# ADC_Level.net
KiCad netlist of a schematic drawn in Altium Designer
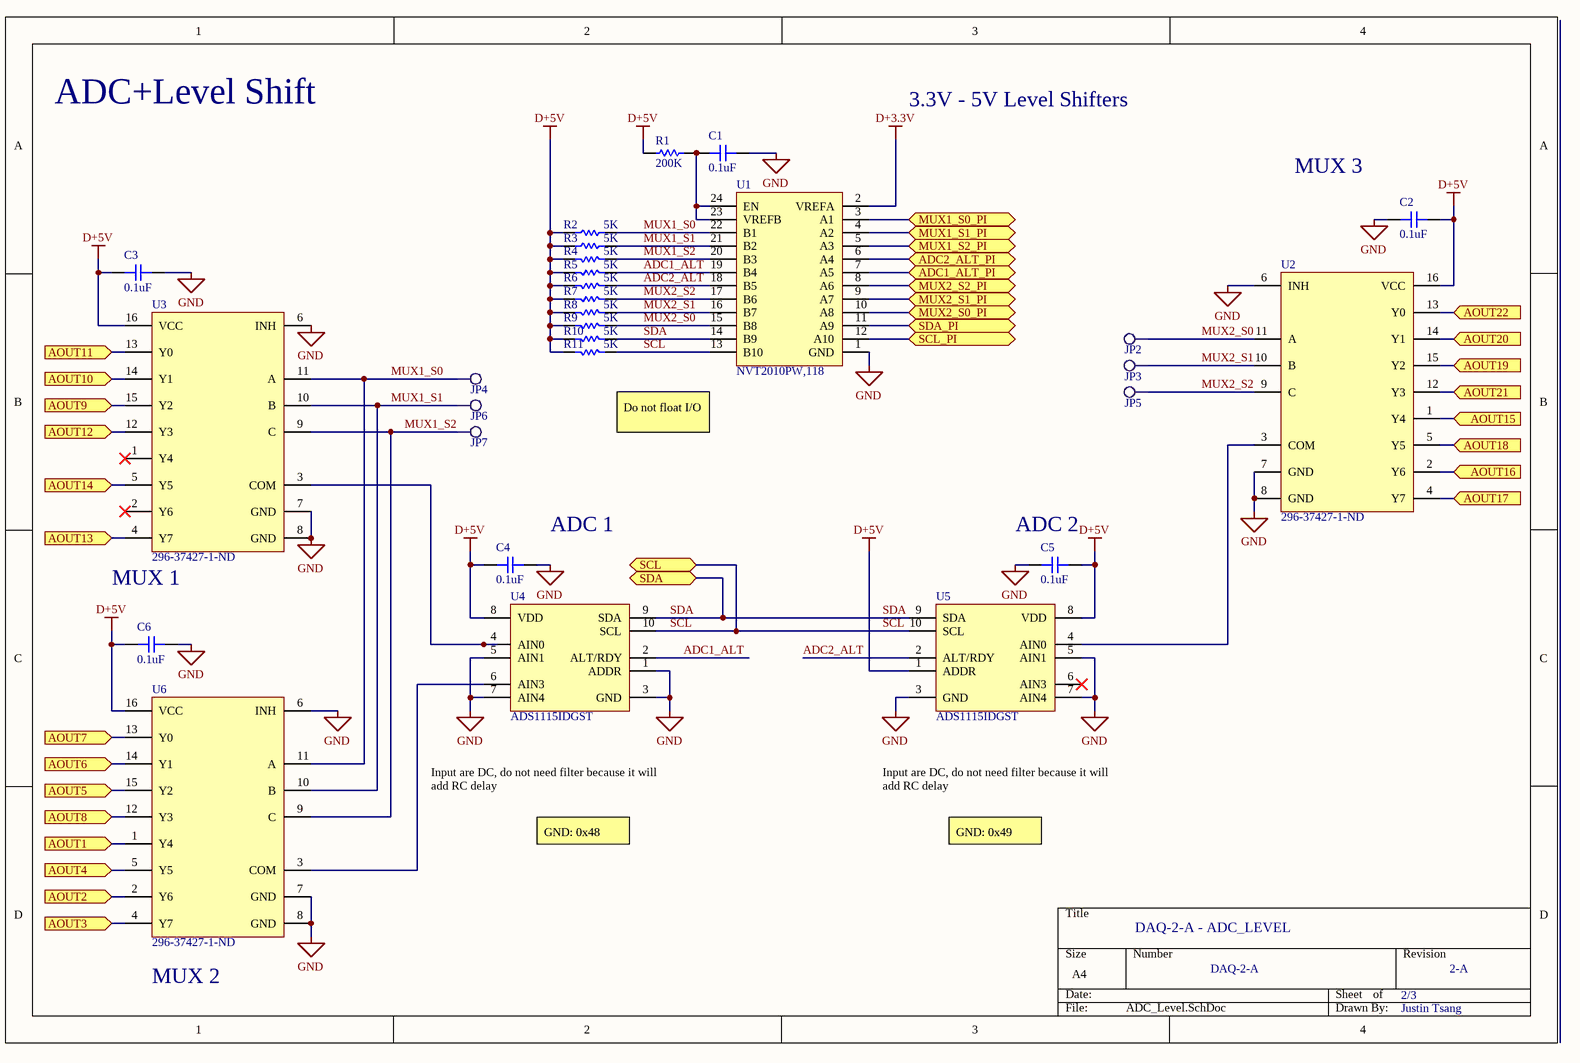
[diagram p0: ADC_Level.SchDoc]

(export (version "E")
  (design (tool "Eeschema 10.0.6"))
  (components
    (comp (ref "C1")
      (value "0.1uF")
      (footprint "CAP-0603")
      (description "CAP CER 0.1UF 16V X7R 0603")
      (fields
        (field (name "MANUFACTURER") "KEMET")
        (field (name "MANUFACTURER PART NUMBER") "C0603C104M4RACTU")
      )
      (libsource (lib "Capacitors") (part "0603-0.1uF-16V"))
    )
    (comp (ref "C2")
      (value "0.1uF")
      (footprint "CAP-0603")
      (description "CAP CER 0.1UF 16V X7R 0603")
      (fields
        (field (name "MANUFACTURER") "KEMET")
        (field (name "MANUFACTURER PART NUMBER") "C0603C104M4RACTU")
      )
      (libsource (lib "Capacitors") (part "0603-0.1uF-16V"))
    )
    (comp (ref "C3")
      (value "0.1uF")
      (footprint "CAP-0603")
      (description "CAP CER 0.1UF 16V X7R 0603")
      (fields
        (field (name "MANUFACTURER") "KEMET")
        (field (name "MANUFACTURER PART NUMBER") "C0603C104M4RACTU")
      )
      (libsource (lib "Capacitors") (part "0603-0.1uF-16V"))
    )
    (comp (ref "C4")
      (value "0.1uF")
      (footprint "CAP-0603")
      (description "CAP CER 0.1UF 16V X7R 0603")
      (fields
        (field (name "MANUFACTURER") "KEMET")
        (field (name "MANUFACTURER PART NUMBER") "C0603C104M4RACTU")
      )
      (libsource (lib "Capacitors") (part "0603-0.1uF-16V"))
    )
    (comp (ref "C5")
      (value "0.1uF")
      (footprint "CAP-0603")
      (description "CAP CER 0.1UF 16V X7R 0603")
      (fields
        (field (name "MANUFACTURER") "KEMET")
        (field (name "MANUFACTURER PART NUMBER") "C0603C104M4RACTU")
      )
      (libsource (lib "Capacitors") (part "0603-0.1uF-16V"))
    )
    (comp (ref "C6")
      (value "0.1uF")
      (footprint "CAP-0603")
      (description "CAP CER 0.1UF 16V X7R 0603")
      (fields
        (field (name "MANUFACTURER") "KEMET")
        (field (name "MANUFACTURER PART NUMBER") "C0603C104M4RACTU")
      )
      (libsource (lib "Capacitors") (part "0603-0.1uF-16V"))
    )
    (comp (ref "JP2")
      (value "Testpoint2")
      (footprint "TP2")
      (description "Single layer pad TP")
      (libsource (lib "Misc") (part "Testpoint2"))
    )
    (comp (ref "JP3")
      (value "Testpoint2")
      (footprint "TP2")
      (description "Single layer pad TP")
      (libsource (lib "Misc") (part "Testpoint2"))
    )
    (comp (ref "JP4")
      (value "Testpoint2")
      (footprint "TP2")
      (description "Single layer pad TP")
      (libsource (lib "Misc") (part "Testpoint2"))
    )
    (comp (ref "JP5")
      (value "Testpoint2")
      (footprint "TP2")
      (description "Single layer pad TP")
      (libsource (lib "Misc") (part "Testpoint2"))
    )
    (comp (ref "JP6")
      (value "Testpoint2")
      (footprint "TP2")
      (description "Single layer pad TP")
      (libsource (lib "Misc") (part "Testpoint2"))
    )
    (comp (ref "JP7")
      (value "Testpoint2")
      (footprint "TP2")
      (description "Single layer pad TP")
      (libsource (lib "Misc") (part "Testpoint2"))
    )
    (comp (ref "R1")
      (value "200K")
      (footprint "RES-0603")
      (description "RES SMD 200K OHM 1% 1/10W 0603")
      (libsource (lib "New_Parts") (part "0603-200KR"))
    )
    (comp (ref "R2")
      (value "5K")
      (footprint "RES-0603")
      (description "RES SMD 4.99K OHM 1% 1/10W 0603")
      (fields
        (field (name "MANUFACTURER") "Bourns")
        (field (name "MANUFACTURER PART NUMBER") "CR0603-FX-4991ELF")
      )
      (libsource (lib "Resistors") (part "0603-5KR"))
    )
    (comp (ref "R3")
      (value "5K")
      (footprint "RES-0603")
      (description "RES SMD 4.99K OHM 1% 1/10W 0603")
      (fields
        (field (name "MANUFACTURER") "Bourns")
        (field (name "MANUFACTURER PART NUMBER") "CR0603-FX-4991ELF")
      )
      (libsource (lib "Resistors") (part "0603-5KR"))
    )
    (comp (ref "R4")
      (value "5K")
      (footprint "RES-0603")
      (description "RES SMD 4.99K OHM 1% 1/10W 0603")
      (fields
        (field (name "MANUFACTURER") "Bourns")
        (field (name "MANUFACTURER PART NUMBER") "CR0603-FX-4991ELF")
      )
      (libsource (lib "Resistors") (part "0603-5KR"))
    )
    (comp (ref "R5")
      (value "5K")
      (footprint "RES-0603")
      (description "RES SMD 4.99K OHM 1% 1/10W 0603")
      (fields
        (field (name "MANUFACTURER") "Bourns")
        (field (name "MANUFACTURER PART NUMBER") "CR0603-FX-4991ELF")
      )
      (libsource (lib "Resistors") (part "0603-5KR"))
    )
    (comp (ref "R6")
      (value "5K")
      (footprint "RES-0603")
      (description "RES SMD 4.99K OHM 1% 1/10W 0603")
      (fields
        (field (name "MANUFACTURER") "Bourns")
        (field (name "MANUFACTURER PART NUMBER") "CR0603-FX-4991ELF")
      )
      (libsource (lib "Resistors") (part "0603-5KR"))
    )
    (comp (ref "R7")
      (value "5K")
      (footprint "RES-0603")
      (description "RES SMD 4.99K OHM 1% 1/10W 0603")
      (fields
        (field (name "MANUFACTURER") "Bourns")
        (field (name "MANUFACTURER PART NUMBER") "CR0603-FX-4991ELF")
      )
      (libsource (lib "Resistors") (part "0603-5KR"))
    )
    (comp (ref "R8")
      (value "5K")
      (footprint "RES-0603")
      (description "RES SMD 4.99K OHM 1% 1/10W 0603")
      (fields
        (field (name "MANUFACTURER") "Bourns")
        (field (name "MANUFACTURER PART NUMBER") "CR0603-FX-4991ELF")
      )
      (libsource (lib "Resistors") (part "0603-5KR"))
    )
    (comp (ref "R9")
      (value "5K")
      (footprint "RES-0603")
      (description "RES SMD 4.99K OHM 1% 1/10W 0603")
      (fields
        (field (name "MANUFACTURER") "Bourns")
        (field (name "MANUFACTURER PART NUMBER") "CR0603-FX-4991ELF")
      )
      (libsource (lib "Resistors") (part "0603-5KR"))
    )
    (comp (ref "R10")
      (value "5K")
      (footprint "RES-0603")
      (description "RES SMD 4.99K OHM 1% 1/10W 0603")
      (fields
        (field (name "MANUFACTURER") "Bourns")
        (field (name "MANUFACTURER PART NUMBER") "CR0603-FX-4991ELF")
      )
      (libsource (lib "Resistors") (part "0603-5KR"))
    )
    (comp (ref "R11")
      (value "5K")
      (footprint "RES-0603")
      (description "RES SMD 4.99K OHM 1% 1/10W 0603")
      (fields
        (field (name "MANUFACTURER") "Bourns")
        (field (name "MANUFACTURER PART NUMBER") "CR0603-FX-4991ELF")
      )
      (libsource (lib "Resistors") (part "0603-5KR"))
    )
    (comp (ref "U1")
      (value "NVT2010PW,118")
      (footprint "TSSOP65P660X110-24")
      (description "NVT2010PW/TSSOP24/REEL13//")
      (fields (field (name "MANUFACTURER") "NXP Semiconductors"))
      (libsource (lib "New_Parts") (part "IC_NVT2010PW"))
    )
    (comp (ref "U2")
      (value "296-37427-1-ND")
      (footprint "16-SOIC")
      (description "IC MUX/DEMUX 8X1 16SOIC")
      (fields
        (field (name "MANUFACTURER") "Texas Instruments")
        (field (name "MANUFACTURER PART NUMBER") "SN74LV4051ATDWRQ1")
      )
      (libsource (lib "") (part "MUX-SN74LV4051ATDWRQ1_1"))
    )
    (comp (ref "U3")
      (value "296-37427-1-ND")
      (footprint "16-SOIC")
      (description "IC MUX/DEMUX 8X1 16SOIC")
      (fields
        (field (name "MANUFACTURER") "Texas Instruments")
        (field (name "MANUFACTURER PART NUMBER") "SN74LV4051ATDWRQ1")
      )
      (libsource (lib "ICs") (part "MUX-SN74LV4051ATDWRQ1"))
    )
    (comp (ref "U4")
      (value "ADS1115IDGST")
      (footprint "VSSOP50P310X310-10P")
      (fields (field (name "MANUFACTURER") "Texas Instruments"))
      (libsource (lib "New_Parts") (part "IC_ADS1115"))
    )
    (comp (ref "U5")
      (value "ADS1115IDGST")
      (footprint "VSSOP50P310X310-10P")
      (fields (field (name "MANUFACTURER") "Texas Instruments"))
      (libsource (lib "") (part "IC_ADS1115_1"))
    )
    (comp (ref "U6")
      (value "296-37427-1-ND")
      (footprint "16-SOIC")
      (description "IC MUX/DEMUX 8X1 16SOIC")
      (fields
        (field (name "MANUFACTURER") "Texas Instruments")
        (field (name "MANUFACTURER PART NUMBER") "SN74LV4051ATDWRQ1")
      )
      (libsource (lib "ICs") (part "MUX-SN74LV4051ATDWRQ1"))
    )
  )
  (nets
    (net (code "1") (name "/ADC1_ALT") (class "Default")
      (node (ref "R5") (pin "2") (pinfunction "2_2") (pintype "passive"))
      (node (ref "U1") (pin "19") (pinfunction "B4_19") (pintype "passive"))
      (node (ref "U4") (pin "2") (pinfunction "ALT/RDY_2") (pintype "passive"))
    )
    (net (code "2") (name "/ADC1_ALT_PI") (class "Default")
      (node (ref "U1") (pin "7") (pinfunction "A5_7") (pintype "passive"))
    )
    (net (code "3") (name "/ADC2_ALT") (class "Default")
      (node (ref "R6") (pin "2") (pinfunction "2_2") (pintype "passive"))
      (node (ref "U1") (pin "18") (pinfunction "B5_18") (pintype "passive"))
      (node (ref "U5") (pin "2") (pinfunction "ALT/RDY_2") (pintype "passive"))
    )
    (net (code "4") (name "/ADC2_ALT_PI") (class "Default")
      (node (ref "U1") (pin "6") (pinfunction "A4_6") (pintype "passive"))
    )
    (net (code "5") (name "/AOUT1") (class "Default")
      (node (ref "U6") (pin "1") (pinfunction "Y4_1") (pintype "passive"))
    )
    (net (code "6") (name "/AOUT2") (class "Default")
      (node (ref "U6") (pin "2") (pinfunction "Y6_2") (pintype "passive"))
    )
    (net (code "7") (name "/AOUT3") (class "Default")
      (node (ref "U6") (pin "4") (pinfunction "Y7_4") (pintype "passive"))
    )
    (net (code "8") (name "/AOUT4") (class "Default")
      (node (ref "U6") (pin "5") (pinfunction "Y5_5") (pintype "passive"))
    )
    (net (code "9") (name "/AOUT5") (class "Default")
      (node (ref "U6") (pin "15") (pinfunction "Y2_15") (pintype "passive"))
    )
    (net (code "10") (name "/AOUT6") (class "Default")
      (node (ref "U6") (pin "14") (pinfunction "Y1_14") (pintype "passive"))
    )
    (net (code "11") (name "/AOUT7") (class "Default")
      (node (ref "U6") (pin "13") (pinfunction "Y0_13") (pintype "passive"))
    )
    (net (code "12") (name "/AOUT8") (class "Default")
      (node (ref "U6") (pin "12") (pinfunction "Y3_12") (pintype "passive"))
    )
    (net (code "13") (name "/AOUT9") (class "Default")
      (node (ref "U3") (pin "15") (pinfunction "Y2_15") (pintype "passive"))
    )
    (net (code "14") (name "/AOUT10") (class "Default")
      (node (ref "U3") (pin "14") (pinfunction "Y1_14") (pintype "passive"))
    )
    (net (code "15") (name "/AOUT11") (class "Default")
      (node (ref "U3") (pin "13") (pinfunction "Y0_13") (pintype "passive"))
    )
    (net (code "16") (name "/AOUT12") (class "Default")
      (node (ref "U3") (pin "12") (pinfunction "Y3_12") (pintype "passive"))
    )
    (net (code "17") (name "/AOUT13") (class "Default")
      (node (ref "U3") (pin "4") (pinfunction "Y7_4") (pintype "passive"))
    )
    (net (code "18") (name "/AOUT14") (class "Default")
      (node (ref "U3") (pin "5") (pinfunction "Y5_5") (pintype "passive"))
    )
    (net (code "19") (name "/AOUT15") (class "Default")
      (node (ref "U2") (pin "1") (pinfunction "Y4_1") (pintype "passive"))
    )
    (net (code "20") (name "/AOUT16") (class "Default")
      (node (ref "U2") (pin "2") (pinfunction "Y6_2") (pintype "passive"))
    )
    (net (code "21") (name "/AOUT17") (class "Default")
      (node (ref "U2") (pin "4") (pinfunction "Y7_4") (pintype "passive"))
    )
    (net (code "22") (name "/AOUT18") (class "Default")
      (node (ref "U2") (pin "5") (pinfunction "Y5_5") (pintype "passive"))
    )
    (net (code "23") (name "/AOUT19") (class "Default")
      (node (ref "U2") (pin "15") (pinfunction "Y2_15") (pintype "passive"))
    )
    (net (code "24") (name "/AOUT20") (class "Default")
      (node (ref "U2") (pin "14") (pinfunction "Y1_14") (pintype "passive"))
    )
    (net (code "25") (name "/AOUT21") (class "Default")
      (node (ref "U2") (pin "12") (pinfunction "Y3_12") (pintype "passive"))
    )
    (net (code "26") (name "/AOUT22") (class "Default")
      (node (ref "U2") (pin "13") (pinfunction "Y0_13") (pintype "passive"))
    )
    (net (code "27") (name "/MUX1_S0") (class "Default")
      (node (ref "JP4") (pin "1") (pinfunction "1_1") (pintype "passive"))
      (node (ref "R2") (pin "2") (pinfunction "2_2") (pintype "passive"))
      (node (ref "U1") (pin "22") (pinfunction "B1_22") (pintype "passive"))
      (node (ref "U3") (pin "11") (pinfunction "A_11") (pintype "passive"))
      (node (ref "U6") (pin "11") (pinfunction "A_11") (pintype "passive"))
    )
    (net (code "28") (name "/MUX1_S0_PI") (class "Default")
      (node (ref "U1") (pin "3") (pinfunction "A1_3") (pintype "passive"))
    )
    (net (code "29") (name "/MUX1_S1") (class "Default")
      (node (ref "JP6") (pin "1") (pinfunction "1_1") (pintype "passive"))
      (node (ref "R3") (pin "2") (pinfunction "2_2") (pintype "passive"))
      (node (ref "U1") (pin "21") (pinfunction "B2_21") (pintype "passive"))
      (node (ref "U3") (pin "10") (pinfunction "B_10") (pintype "passive"))
      (node (ref "U6") (pin "10") (pinfunction "B_10") (pintype "passive"))
    )
    (net (code "30") (name "/MUX1_S1_PI") (class "Default")
      (node (ref "U1") (pin "4") (pinfunction "A2_4") (pintype "passive"))
    )
    (net (code "31") (name "/MUX1_S2") (class "Default")
      (node (ref "JP7") (pin "1") (pinfunction "1_1") (pintype "passive"))
      (node (ref "R4") (pin "2") (pinfunction "2_2") (pintype "passive"))
      (node (ref "U1") (pin "20") (pinfunction "B3_20") (pintype "passive"))
      (node (ref "U3") (pin "9") (pinfunction "C_9") (pintype "passive"))
      (node (ref "U6") (pin "9") (pinfunction "C_9") (pintype "passive"))
    )
    (net (code "32") (name "/MUX1_S2_PI") (class "Default")
      (node (ref "U1") (pin "5") (pinfunction "A3_5") (pintype "passive"))
    )
    (net (code "33") (name "/MUX2_S0") (class "Default")
      (node (ref "JP2") (pin "1") (pinfunction "1_1") (pintype "passive"))
      (node (ref "R9") (pin "2") (pinfunction "2_2") (pintype "passive"))
      (node (ref "U1") (pin "15") (pinfunction "B8_15") (pintype "passive"))
      (node (ref "U2") (pin "11") (pinfunction "A_11") (pintype "passive"))
    )
    (net (code "34") (name "/MUX2_S0_PI") (class "Default")
      (node (ref "U1") (pin "10") (pinfunction "A8_10") (pintype "passive"))
    )
    (net (code "35") (name "/MUX2_S1") (class "Default")
      (node (ref "JP3") (pin "1") (pinfunction "1_1") (pintype "passive"))
      (node (ref "R8") (pin "2") (pinfunction "2_2") (pintype "passive"))
      (node (ref "U1") (pin "16") (pinfunction "B7_16") (pintype "passive"))
      (node (ref "U2") (pin "10") (pinfunction "B_10") (pintype "passive"))
    )
    (net (code "36") (name "/MUX2_S1_PI") (class "Default")
      (node (ref "U1") (pin "9") (pinfunction "A7_9") (pintype "passive"))
    )
    (net (code "37") (name "/MUX2_S2") (class "Default")
      (node (ref "JP5") (pin "1") (pinfunction "1_1") (pintype "passive"))
      (node (ref "R7") (pin "2") (pinfunction "2_2") (pintype "passive"))
      (node (ref "U1") (pin "17") (pinfunction "B6_17") (pintype "passive"))
      (node (ref "U2") (pin "9") (pinfunction "C_9") (pintype "passive"))
    )
    (net (code "38") (name "/MUX2_S2_PI") (class "Default")
      (node (ref "U1") (pin "8") (pinfunction "A6_8") (pintype "passive"))
    )
    (net (code "39") (name "/SCL") (class "Default")
      (node (ref "R11") (pin "2") (pinfunction "2_2") (pintype "passive"))
      (node (ref "U1") (pin "13") (pinfunction "B10_13") (pintype "passive"))
      (node (ref "U4") (pin "10") (pinfunction "SCL_10") (pintype "passive"))
      (node (ref "U5") (pin "10") (pinfunction "SCL_10") (pintype "passive"))
    )
    (net (code "40") (name "/SCL_PI") (class "Default")
      (node (ref "U1") (pin "12") (pinfunction "A10_12") (pintype "passive"))
    )
    (net (code "41") (name "/SDA") (class "Default")
      (node (ref "R10") (pin "1") (pinfunction "1_1") (pintype "passive"))
      (node (ref "U1") (pin "14") (pinfunction "B9_14") (pintype "passive"))
      (node (ref "U4") (pin "9") (pinfunction "SDA_9") (pintype "passive"))
      (node (ref "U5") (pin "9") (pinfunction "SDA_9") (pintype "passive"))
    )
    (net (code "42") (name "/SDA_PI") (class "Default")
      (node (ref "U1") (pin "11") (pinfunction "A9_11") (pintype "passive"))
    )
    (net (code "43") (name "D+3.3V") (class "Default")
      (node (ref "U1") (pin "2") (pinfunction "VREFA_2") (pintype "passive"))
    )
    (net (code "44") (name "D+5V") (class "Default")
      (node (ref "C2") (pin "2") (pinfunction "2_2") (pintype "passive"))
      (node (ref "C3") (pin "2") (pinfunction "2_2") (pintype "passive"))
      (node (ref "C4") (pin "2") (pinfunction "2_2") (pintype "passive"))
      (node (ref "C5") (pin "2") (pinfunction "2_2") (pintype "passive"))
      (node (ref "C6") (pin "2") (pinfunction "2_2") (pintype "passive"))
      (node (ref "R1") (pin "2") (pinfunction "2_2") (pintype "passive"))
      (node (ref "R10") (pin "2") (pinfunction "2_2") (pintype "passive"))
      (node (ref "R11") (pin "1") (pinfunction "1_1") (pintype "passive"))
      (node (ref "R2") (pin "1") (pinfunction "1_1") (pintype "passive"))
      (node (ref "R3") (pin "1") (pinfunction "1_1") (pintype "passive"))
      (node (ref "R4") (pin "1") (pinfunction "1_1") (pintype "passive"))
      (node (ref "R5") (pin "1") (pinfunction "1_1") (pintype "passive"))
      (node (ref "R6") (pin "1") (pinfunction "1_1") (pintype "passive"))
      (node (ref "R7") (pin "1") (pinfunction "1_1") (pintype "passive"))
      (node (ref "R8") (pin "1") (pinfunction "1_1") (pintype "passive"))
      (node (ref "R9") (pin "1") (pinfunction "1_1") (pintype "passive"))
      (node (ref "U2") (pin "16") (pinfunction "VCC_16") (pintype "passive"))
      (node (ref "U3") (pin "16") (pinfunction "VCC_16") (pintype "passive"))
      (node (ref "U4") (pin "8") (pinfunction "VDD_8") (pintype "passive"))
      (node (ref "U5") (pin "1") (pinfunction "ADDR_1") (pintype "passive"))
      (node (ref "U5") (pin "8") (pinfunction "VDD_8") (pintype "passive"))
      (node (ref "U6") (pin "16") (pinfunction "VCC_16") (pintype "passive"))
    )
    (net (code "45") (name "GND") (class "Default")
      (node (ref "C1") (pin "1") (pinfunction "1_1") (pintype "passive"))
      (node (ref "C2") (pin "1") (pinfunction "1_1") (pintype "passive"))
      (node (ref "C3") (pin "1") (pinfunction "1_1") (pintype "passive"))
      (node (ref "C4") (pin "1") (pinfunction "1_1") (pintype "passive"))
      (node (ref "C5") (pin "1") (pinfunction "1_1") (pintype "passive"))
      (node (ref "C6") (pin "1") (pinfunction "1_1") (pintype "passive"))
      (node (ref "U1") (pin "1") (pinfunction "GND_1") (pintype "passive"))
      (node (ref "U2") (pin "6") (pinfunction "INH_6") (pintype "passive"))
      (node (ref "U2") (pin "7") (pinfunction "GND_7") (pintype "passive"))
      (node (ref "U2") (pin "8") (pinfunction "GND_8") (pintype "passive"))
      (node (ref "U3") (pin "6") (pinfunction "INH_6") (pintype "passive"))
      (node (ref "U3") (pin "7") (pinfunction "GND_7") (pintype "passive"))
      (node (ref "U3") (pin "8") (pinfunction "GND_8") (pintype "passive"))
      (node (ref "U4") (pin "1") (pinfunction "ADDR_1") (pintype "passive"))
      (node (ref "U4") (pin "3") (pinfunction "GND_3") (pintype "passive"))
      (node (ref "U4") (pin "5") (pinfunction "AIN1_5") (pintype "passive"))
      (node (ref "U4") (pin "7") (pinfunction "AIN4_7") (pintype "passive"))
      (node (ref "U5") (pin "3") (pinfunction "GND_3") (pintype "passive"))
      (node (ref "U5") (pin "5") (pinfunction "AIN1_5") (pintype "passive"))
      (node (ref "U5") (pin "7") (pinfunction "AIN4_7") (pintype "passive"))
      (node (ref "U6") (pin "6") (pinfunction "INH_6") (pintype "passive"))
      (node (ref "U6") (pin "7") (pinfunction "GND_7") (pintype "passive"))
      (node (ref "U6") (pin "8") (pinfunction "GND_8") (pintype "passive"))
    )
    (net (code "46") (name "Net-(U1-EN)") (class "Default")
      (node (ref "C1") (pin "2") (pinfunction "2_2") (pintype "passive"))
      (node (ref "R1") (pin "1") (pinfunction "1_1") (pintype "passive"))
      (node (ref "U1") (pin "23") (pinfunction "VREFB_23") (pintype "passive"))
      (node (ref "U1") (pin "24") (pinfunction "EN_24") (pintype "passive"))
    )
    (net (code "47") (name "Net-(U2-COM)") (class "Default")
      (node (ref "U2") (pin "3") (pinfunction "COM_3") (pintype "passive"))
      (node (ref "U5") (pin "4") (pinfunction "AIN0_4") (pintype "passive"))
    )
    (net (code "48") (name "Net-(U3-COM)") (class "Default")
      (node (ref "U3") (pin "3") (pinfunction "COM_3") (pintype "passive"))
      (node (ref "U4") (pin "4") (pinfunction "AIN0_4") (pintype "passive"))
    )
    (net (code "49") (name "Net-(U4-AIN3)") (class "Default")
      (node (ref "U4") (pin "6") (pinfunction "AIN3_6") (pintype "passive"))
      (node (ref "U6") (pin "3") (pinfunction "COM_3") (pintype "passive"))
    )
    (net (code "50") (name "unconnected-(U3-Y4-Pad1)") (class "Default")
      (node (ref "U3") (pin "1") (pinfunction "Y4_1") (pintype "passive+no_connect"))
    )
    (net (code "51") (name "unconnected-(U3-Y6-Pad2)") (class "Default")
      (node (ref "U3") (pin "2") (pinfunction "Y6_2") (pintype "passive+no_connect"))
    )
    (net (code "52") (name "unconnected-(U5-AIN3-Pad6)") (class "Default")
      (node (ref "U5") (pin "6") (pinfunction "AIN3_6") (pintype "passive+no_connect"))
    )
  )
)
